# CE842170047_SHEET1.net
KiCad netlist of a schematic drawn in Altium Designer
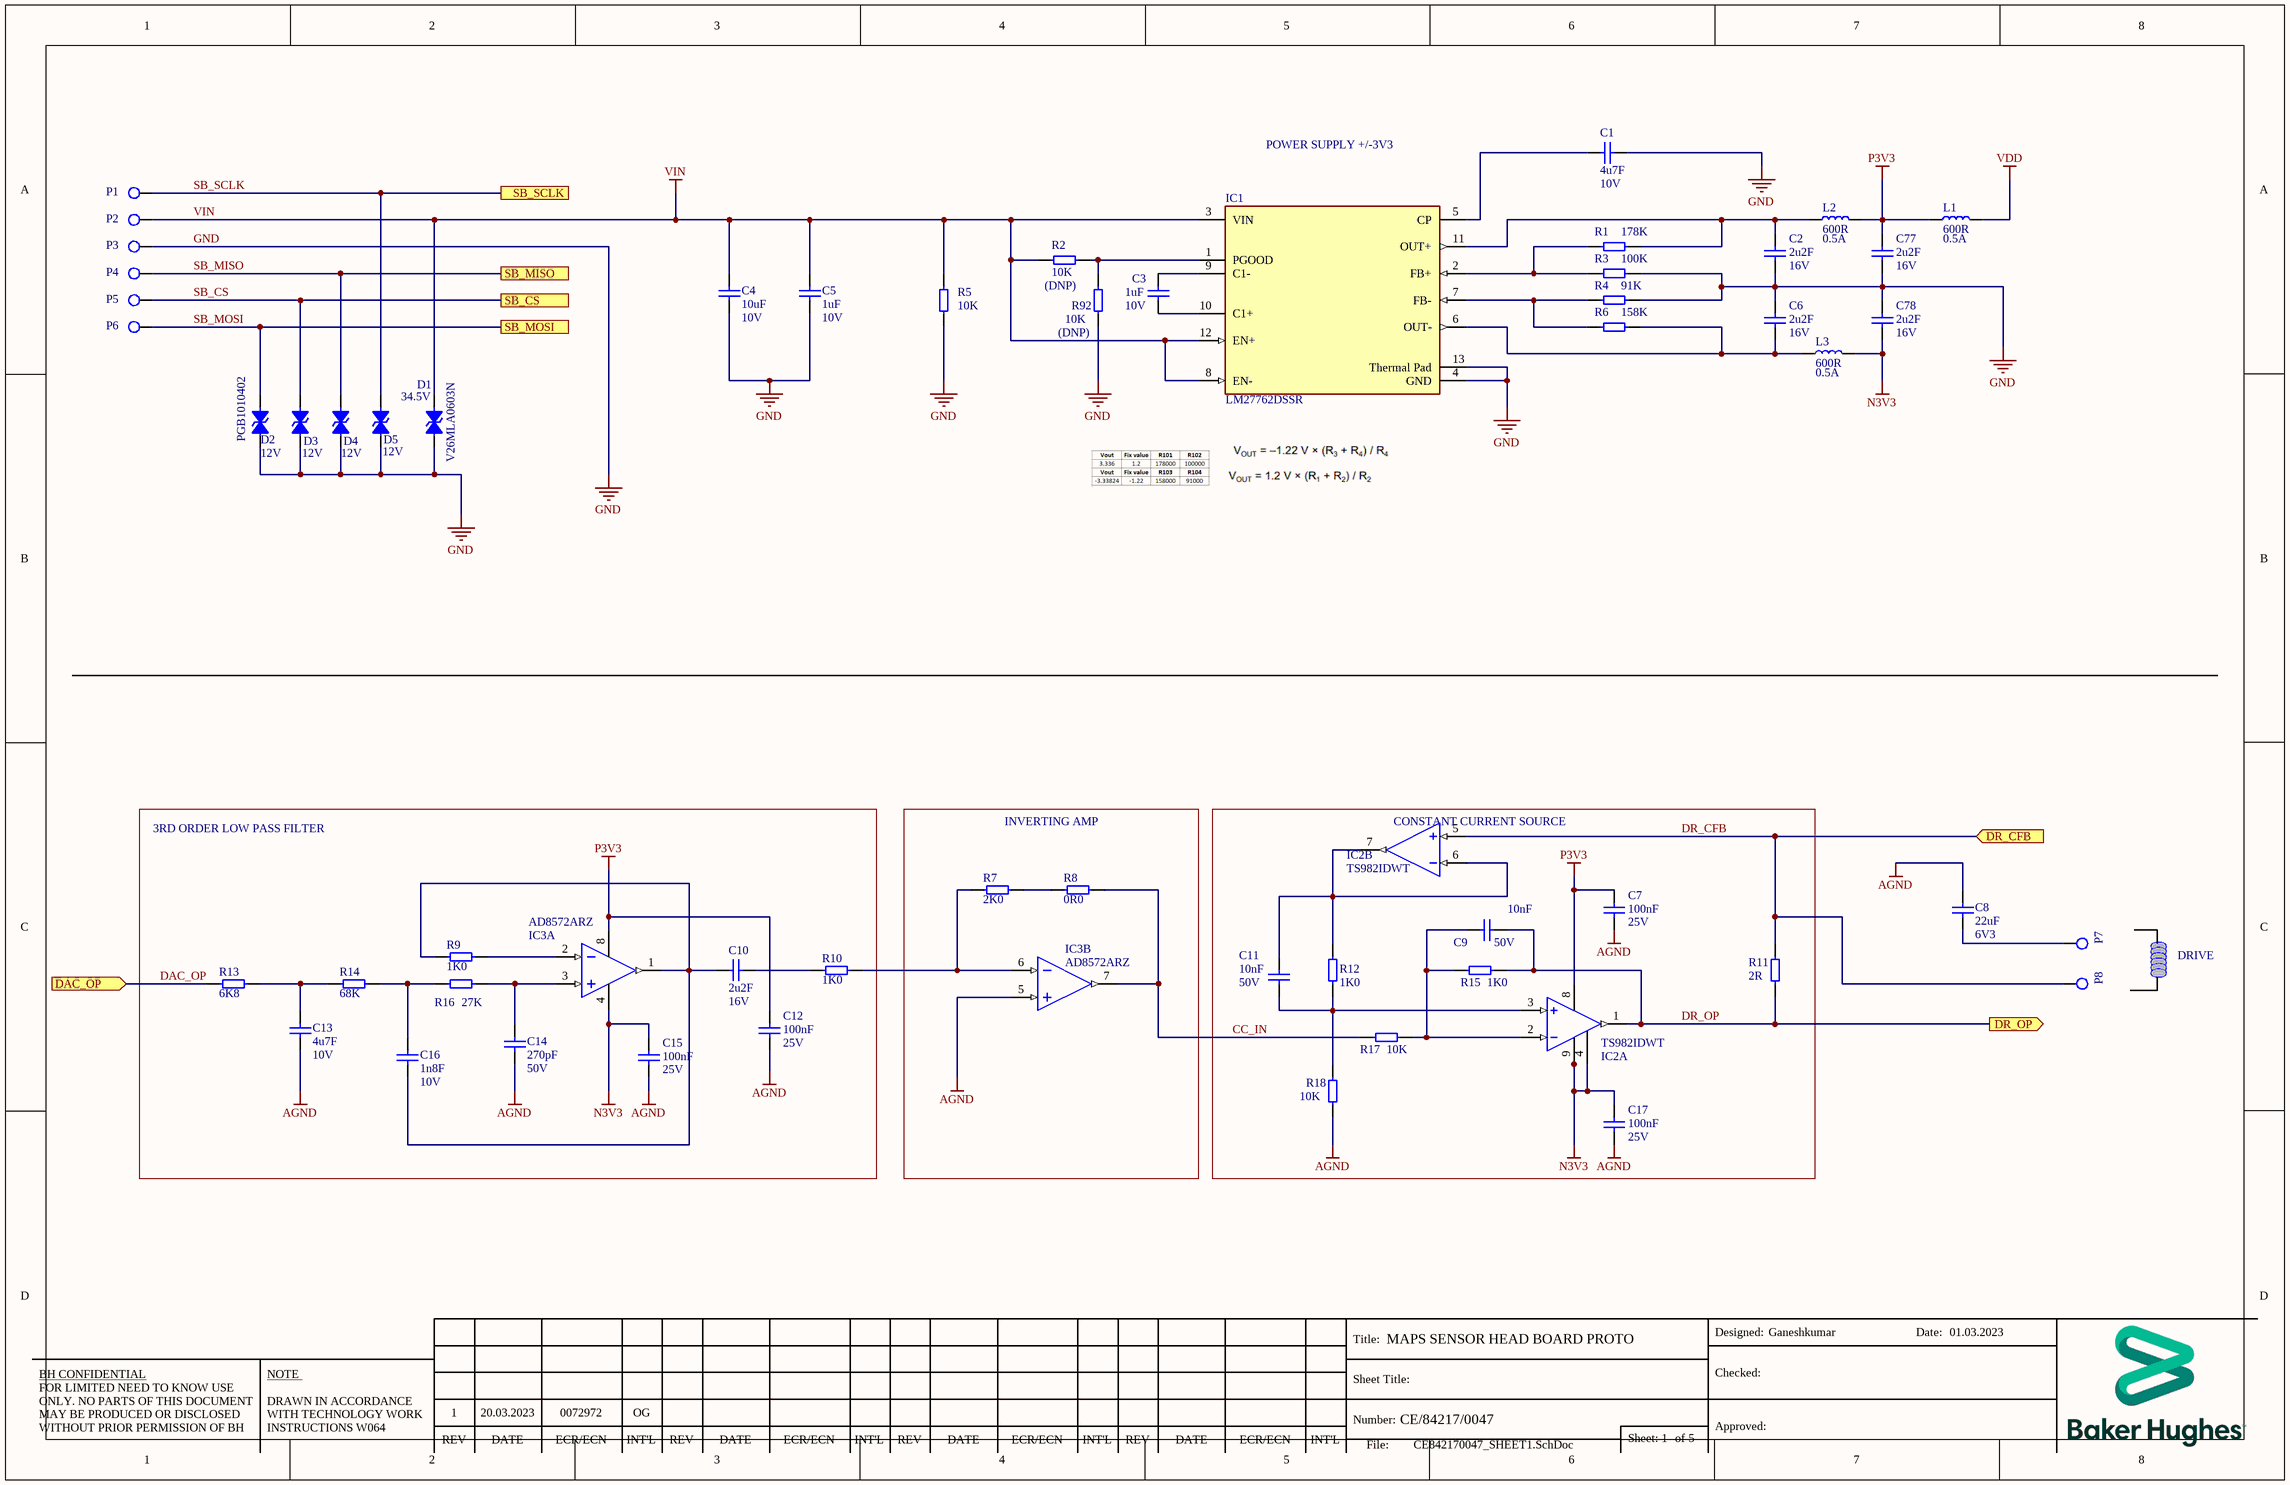
[diagram p0: CE842170047_SHEET1.SchDoc]

(export (version "E")
  (design (tool "Eeschema 10.0.6"))
  (components
    (comp (ref "C1")
      (value "4u7F")
      (footprint "C0603")
      (description "CAPACITOR_4u7F_10%_10V_0603")
      (fields
        (field (name "VOLTAGE") "10V")
        (field (name "PII_PARTNUMBER") "KK/96159/2666")
        (field (name "TOLERANCE") "10%")
      )
      (libsource (lib "AltiumComponents") (part "CAP_GENERIC"))
    )
    (comp (ref "C2")
      (value "2u2F")
      (footprint "C0603")
      (description "CAPACITOR CERAMIC 0603 16V 10% X5R 2u2")
      (fields
        (field (name "VOLTAGE") "16V")
        (field (name "PII_PARTNUMBER") "KK/96159/3634")
        (field (name "TOLERANCE") "10%")
      )
      (libsource (lib "AltiumComponents") (part "CAP_GENERIC"))
    )
    (comp (ref "C3")
      (value "1uF")
      (footprint "C0603")
      (description "CAPACITOR_1uF_+10%_10V_603")
      (fields
        (field (name "VOLTAGE") "10V")
        (field (name "PII_PARTNUMBER") "KK/96159/2601")
        (field (name "TOLERANCE") "10%")
      )
      (libsource (lib "AltiumComponents") (part "CAP_GENERIC"))
    )
    (comp (ref "C4")
      (value "10uF")
      (footprint "C0603")
      (description "CAPACITOR_10uF_10%_10V_0603")
      (fields
        (field (name "VOLTAGE") "10V")
        (field (name "PII_PARTNUMBER") "KK/96159/3701")
        (field (name "TOLERANCE") "10%")
      )
      (libsource (lib "AltiumComponents") (part "CAP_GENERIC"))
    )
    (comp (ref "C5")
      (value "1uF")
      (footprint "C0603")
      (description "CAPACITOR_1uF_+10%_10V_603")
      (fields
        (field (name "VOLTAGE") "10V")
        (field (name "PII_PARTNUMBER") "KK/96159/2601")
        (field (name "TOLERANCE") "10%")
      )
      (libsource (lib "AltiumComponents") (part "CAP_GENERIC"))
    )
    (comp (ref "C6")
      (value "2u2F")
      (footprint "C0603")
      (description "CAPACITOR CERAMIC 0603 16V 10% X5R 2u2")
      (fields
        (field (name "VOLTAGE") "16V")
        (field (name "PII_PARTNUMBER") "KK/96159/3634")
        (field (name "TOLERANCE") "10%")
      )
      (libsource (lib "AltiumComponents") (part "CAP_GENERIC"))
    )
    (comp (ref "C7")
      (value "100nF")
      (footprint "C0603")
      (description "CAPACITOR_100nF_+10%_25V_603")
      (fields
        (field (name "VOLTAGE") "25V")
        (field (name "PII_PARTNUMBER") "KK/96159/4501")
        (field (name "TOLERANCE") "10%")
      )
      (libsource (lib "AltiumComponents") (part "CAP_GENERIC"))
    )
    (comp (ref "C8")
      (value "22uF")
      (footprint "C0805")
      (description "CAPACITOR_22uF_20%_6V3_0805")
      (fields
        (field (name "VOLTAGE") "6V3")
        (field (name "PII_PARTNUMBER") "KK/96160/0734")
        (field (name "TOLERANCE") "20%")
      )
      (libsource (lib "AltiumComponents") (part "CAP_GENERIC"))
    )
    (comp (ref "C9")
      (value "10nF")
      (footprint "C0603")
      (description "CAPACITOR CERAMIC 0603 50V 10% X7R 10nF")
      (fields
        (field (name "VOLTAGE") "50V")
        (field (name "PII_PARTNUMBER") "KK/96159/0401")
        (field (name "TOLERANCE") "10%")
      )
      (libsource (lib "AltiumComponents") (part "CAP_GENERIC"))
    )
    (comp (ref "C10")
      (value "2u2F")
      (footprint "C0603")
      (description "CAPACITOR CERAMIC 0603 16V 10% X5R 2u2")
      (fields
        (field (name "VOLTAGE") "16V")
        (field (name "PII_PARTNUMBER") "KK/96159/3634")
        (field (name "TOLERANCE") "10%")
      )
      (libsource (lib "AltiumComponents") (part "CAP_GENERIC"))
    )
    (comp (ref "C11")
      (value "10nF")
      (footprint "C0603")
      (description "CAPACITOR CERAMIC 0603 50V 10% X7R 10nF")
      (fields
        (field (name "VOLTAGE") "50V")
        (field (name "PII_PARTNUMBER") "KK/96159/0401")
        (field (name "TOLERANCE") "10%")
      )
      (libsource (lib "AltiumComponents") (part "CAP_GENERIC"))
    )
    (comp (ref "C12")
      (value "100nF")
      (footprint "C0603")
      (description "CAPACITOR_100nF_+10%_25V_603")
      (fields
        (field (name "VOLTAGE") "25V")
        (field (name "PII_PARTNUMBER") "KK/96159/4501")
        (field (name "TOLERANCE") "10%")
      )
      (libsource (lib "AltiumComponents") (part "CAP_GENERIC"))
    )
    (comp (ref "C13")
      (value "4u7F")
      (footprint "C0603")
      (description "CAPACITOR_4u7F_10%_10V_0603")
      (fields
        (field (name "VOLTAGE") "10V")
        (field (name "PII_PARTNUMBER") "KK/96159/2666")
        (field (name "TOLERANCE") "10%")
      )
      (libsource (lib "AltiumComponents") (part "CAP_GENERIC"))
    )
    (comp (ref "C14")
      (value "270pF")
      (footprint "C0603")
      (description "CAPACITOR CER 0603 270pF 10% 50V X5R")
      (fields
        (field (name "VOLTAGE") "50V")
        (field (name "PII_PARTNUMBER") "KK/96159/0243")
        (field (name "TOLERANCE") "10%")
      )
      (libsource (lib "AltiumComponents") (part "CAP_GENERIC"))
    )
    (comp (ref "C15")
      (value "100nF")
      (footprint "C0603")
      (description "CAPACITOR_100nF_+10%_25V_603")
      (fields
        (field (name "VOLTAGE") "25V")
        (field (name "PII_PARTNUMBER") "KK/96159/4501")
        (field (name "TOLERANCE") "10%")
      )
      (libsource (lib "AltiumComponents") (part "CAP_GENERIC"))
    )
    (comp (ref "C16")
      (value "1n8F")
      (footprint "C0603")
      (description "CAPACITOR CER 0603 1n8F 10% 10V X5R")
      (fields
        (field (name "VOLTAGE") "10V")
        (field (name "PII_PARTNUMBER") "KK/96159/0325")
        (field (name "TOLERANCE") "10%")
      )
      (libsource (lib "AltiumComponents") (part "CAP_GENERIC"))
    )
    (comp (ref "C17")
      (value "100nF")
      (footprint "C0603")
      (description "CAPACITOR_100nF_+10%_25V_603")
      (fields
        (field (name "VOLTAGE") "25V")
        (field (name "PII_PARTNUMBER") "KK/96159/4501")
        (field (name "TOLERANCE") "10%")
      )
      (libsource (lib "AltiumComponents") (part "CAP_GENERIC"))
    )
    (comp (ref "C77")
      (value "2u2F")
      (footprint "C0603")
      (description "CAPACITOR CERAMIC 0603 16V 10% X5R 2u2")
      (fields
        (field (name "VOLTAGE") "16V")
        (field (name "PII_PARTNUMBER") "KK/96159/3634")
        (field (name "TOLERANCE") "10%")
      )
      (libsource (lib "AltiumComponents") (part "CAP_GENERIC"))
    )
    (comp (ref "C78")
      (value "2u2F")
      (footprint "C0603")
      (description "CAPACITOR CERAMIC 0603 16V 10% X5R 2u2")
      (fields
        (field (name "VOLTAGE") "16V")
        (field (name "PII_PARTNUMBER") "KK/96159/3634")
        (field (name "TOLERANCE") "10%")
      )
      (libsource (lib "AltiumComponents") (part "CAP_GENERIC"))
    )
    (comp (ref "D1")
      (value "34.5V")
      (footprint "R0603")
      (description "TVS,SMD,LITTLEFUSE,V26MLA0603N[20-26V]")
      (fields
        (field (name "MF_PARTNUMBER") "V26MLA0603N")
        (field (name "PII_PARTNUMBER") "KK/95070/0035")
        (field (name "VOLTAGE") "26V")
      )
      (libsource (lib "AltiumComponents") (part "TVS_DIODE_BIDIR"))
    )
    (comp (ref "D2")
      (value "KK/95070/0036")
      (footprint "ESD0402")
      (description "SUPPRESSOR ESD,SMD,0402,12VDC,LIF,PGB1010402")
      (fields
        (field (name "MF_PARTNUMBER") "PGB1010402")
        (field (name "VOLTAGE") "12V")
        (field (name "MANUFACTURER") "LITTELFUSE")
      )
      (libsource (lib "AltiumComponents") (part "TVS_DIODE_BIDIR"))
    )
    (comp (ref "D3")
      (value "KK/95070/0036")
      (footprint "ESD0402")
      (description "SUPPRESSOR ESD,SMD,0402,12VDC,LIF,PGB1010402")
      (fields
        (field (name "MF_PARTNUMBER") "PGB1010402")
        (field (name "VOLTAGE") "12V")
        (field (name "MANUFACTURER") "LITTELFUSE")
      )
      (libsource (lib "AltiumComponents") (part "TVS_DIODE_BIDIR"))
    )
    (comp (ref "D4")
      (value "KK/95070/0036")
      (footprint "ESD0402")
      (description "SUPPRESSOR ESD,SMD,0402,12VDC,LIF,PGB1010402")
      (fields
        (field (name "MF_PARTNUMBER") "PGB1010402")
        (field (name "VOLTAGE") "12V")
        (field (name "MANUFACTURER") "LITTELFUSE")
      )
      (libsource (lib "AltiumComponents") (part "TVS_DIODE_BIDIR"))
    )
    (comp (ref "D5")
      (value "KK/95070/0036")
      (footprint "ESD0402")
      (description "SUPPRESSOR ESD,SMD,0402,12VDC,LIF,PGB1010402")
      (fields
        (field (name "MF_PARTNUMBER") "PGB1010402")
        (field (name "VOLTAGE") "12V")
        (field (name "MANUFACTURER") "LITTELFUSE")
      )
      (libsource (lib "AltiumComponents") (part "TVS_DIODE_BIDIR"))
    )
    (comp (ref "IC1")
      (value "KK/95311/0117")
      (footprint "WSON-12")
      (description "SWITCHING REGULATOR")
      (fields
        (field (name "MANUFACTURER") "TEXAS INSTRUMENTS")
        (field (name "MANUFACTURER PART NUMBER") "LM27762DSSR")
        (field (name "MF_PARTNUMBER") "LM27762DSSR")
      )
      (libsource (lib "AltiumComponents") (part "LM27762"))
    )
    (comp (ref "IC2")
      (value "KK/95312/0246")
      (footprint "SOIC-8_EP")
      (description "DUAL BIPOLAR OPERATIONAL AMPLIFIER")
      (fields
        (field (name "MP") "TS982IDWT")
        (field (name "MF_PARTNUMBER") "TS982IDWT")
        (field (name "VOLTAGE") "5.5V")
      )
      (libsource (lib "AltiumComponents") (part "TS982"))
    )
    (comp (ref "IC3")
      (value "KK/95312/0244")
      (footprint "SOIC-8")
      (description "DUAL RAIL to RAIL OP AMP")
      (fields
        (field (name "MANUFACTURER") "Analog Devices")
        (field (name "GENERIC PART NUMBER") "AD8572")
        (field (name "MF_PARTNUMBER") "AD8572ARZ")
      )
      (libsource (lib "AltiumComponents") (part "AD8572"))
    )
    (comp (ref "L1")
      (value "600R")
      (footprint "L0603")
      (description "FERRIT BEADS 0603 600R 0.5A 25%")
      (fields
        (field (name "PII_PARTNUMBER") "KK/97900/1033")
        (field (name "MF_PARTNUMBER") "742863160")
        (field (name "POWER") "0.5A")
      )
      (libsource (lib "AltiumComponents") (part "INDUCTOR_GENERIC"))
    )
    (comp (ref "L2")
      (value "600R")
      (footprint "L0603")
      (description "FERRIT BEADS 0603 600R 0.5A 25%")
      (fields
        (field (name "PII_PARTNUMBER") "KK/97900/1033")
        (field (name "MF_PARTNUMBER") "742863160")
        (field (name "POWER") "0.5A")
      )
      (libsource (lib "AltiumComponents") (part "INDUCTOR_GENERIC"))
    )
    (comp (ref "L3")
      (value "600R")
      (footprint "L0603")
      (description "FERRIT BEADS 0603 600R 0.5A 25%")
      (fields
        (field (name "PII_PARTNUMBER") "KK/97900/1033")
        (field (name "MF_PARTNUMBER") "742863160")
        (field (name "POWER") "0.5A")
      )
      (libsource (lib "AltiumComponents") (part "INDUCTOR_GENERIC"))
    )
    (comp (ref "P1")
      (value "TESTPAD1")
      (footprint "P0.8xH0.5")
      (description "P0.8 X H0.5 X 0.9SM")
      (fields (field (name "MANUFACTURER") "PCB MANUFACTURER"))
      (libsource (lib "AltiumComponents") (part "TP_GENERIC"))
    )
    (comp (ref "P2")
      (value "TESTPAD1")
      (footprint "P0.8xH0.5")
      (description "P0.8 X H0.5 X 0.9SM")
      (fields (field (name "MANUFACTURER") "PCB MANUFACTURER"))
      (libsource (lib "AltiumComponents") (part "TP_GENERIC"))
    )
    (comp (ref "P3")
      (value "TESTPAD1")
      (footprint "P0.8xH0.5")
      (description "P0.8 X H0.5 X 0.9SM")
      (fields (field (name "MANUFACTURER") "PCB MANUFACTURER"))
      (libsource (lib "AltiumComponents") (part "TP_GENERIC"))
    )
    (comp (ref "P4")
      (value "TESTPAD1")
      (footprint "P0.8xH0.5")
      (description "P0.8 X H0.5 X 0.9SM")
      (fields (field (name "MANUFACTURER") "PCB MANUFACTURER"))
      (libsource (lib "AltiumComponents") (part "TP_GENERIC"))
    )
    (comp (ref "P5")
      (value "TESTPAD1")
      (footprint "P0.8xH0.5")
      (description "P0.8 X H0.5 X 0.9SM")
      (fields (field (name "MANUFACTURER") "PCB MANUFACTURER"))
      (libsource (lib "AltiumComponents") (part "TP_GENERIC"))
    )
    (comp (ref "P6")
      (value "TESTPAD1")
      (footprint "P0.8xH0.5")
      (description "P0.8 X H0.5 X 0.9SM")
      (fields (field (name "MANUFACTURER") "PCB MANUFACTURER"))
      (libsource (lib "AltiumComponents") (part "TP_GENERIC"))
    )
    (comp (ref "P7")
      (value "TESTPAD1")
      (footprint "P0.8xH0.5")
      (description "P0.8 X H0.5 X 0.9SM")
      (fields (field (name "MANUFACTURER") "PCB MANUFACTURER"))
      (libsource (lib "AltiumComponents") (part "TP_GENERIC"))
    )
    (comp (ref "P8")
      (value "TESTPAD1")
      (footprint "P0.8xH0.5")
      (description "P0.8 X H0.5 X 0.9SM")
      (fields (field (name "MANUFACTURER") "PCB MANUFACTURER"))
      (libsource (lib "AltiumComponents") (part "TP_GENERIC"))
    )
    (comp (ref "R1")
      (value "178K")
      (footprint "R0603")
      (description "RESISTOR 0603 0.063W 0.1% 178K")
      (fields (field (name "PII_PARTNUMBER") "KK/96059/0725") (field (name "TOLERANCE") "0.1%"))
      (libsource (lib "AltiumComponents") (part "RES_GENERIC"))
    )
    (comp (ref "R2")
      (value "10K")
      (footprint "R0603")
      (description "RESISTOR_10K_1%_0603J_63mW")
      (fields (field (name "PII_PARTNUMBER") "KK/96059/0601") (field (name "TOLERANCE") "1%"))
      (libsource (lib "AltiumComponents") (part "RES_GENERIC"))
    )
    (comp (ref "R3")
      (value "100K")
      (footprint "R0603")
      (description "RESISTOR_100K_1%_0603J_63mW")
      (fields (field (name "PII_PARTNUMBER") "KK/96059/0701") (field (name "TOLERANCE") "1%"))
      (libsource (lib "AltiumComponents") (part "RES_GENERIC"))
    )
    (comp (ref "R4")
      (value "91K")
      (footprint "R0603")
      (description "RESISTOR 0603 0.063W 1% 91K")
      (fields (field (name "PII_PARTNUMBER") "KK/96059/1693") (field (name "TOLERANCE") "1%"))
      (libsource (lib "AltiumComponents") (part "RES_GENERIC"))
    )
    (comp (ref "R5")
      (value "10K")
      (footprint "R0603")
      (description "RESISTOR_10K_1%_0603J_63mW")
      (fields (field (name "PII_PARTNUMBER") "KK/96059/0601") (field (name "TOLERANCE") "1%"))
      (libsource (lib "") (part "RES_GENERIC_3"))
    )
    (comp (ref "R6")
      (value "158K")
      (footprint "R0603")
      (description "RESISTOR_158K_1%_0603J_63mW")
      (fields (field (name "PII_PARTNUMBER") "KK/96059/0720") (field (name "TOLERANCE") "1%"))
      (libsource (lib "AltiumComponents") (part "RES_GENERIC"))
    )
    (comp (ref "R7")
      (value "2K0")
      (footprint "R0603")
      (description "RESISTOR_2K_1%_0603J_63m2")
      (fields (field (name "PII_PARTNUMBER") "KK/96059/0530") (field (name "TOLERANCE") "1%"))
      (libsource (lib "AltiumComponents") (part "RES_GENERIC"))
    )
    (comp (ref "R8")
      (value "0R0")
      (footprint "R0603")
      (description "ZERO OHM LINK")
      (fields (field (name "PII_PARTNUMBER") "KK/96059/0000") (field (name "POWER") "63mW"))
      (libsource (lib "AltiumComponents") (part "RES_GENERIC"))
    )
    (comp (ref "R9")
      (value "1K0")
      (footprint "R0603")
      (description "RESISTOR_1K0_1%_0603J_63mW")
      (fields (field (name "PII_PARTNUMBER") "KK/96059/0501") (field (name "TOLERANCE") "1%"))
      (libsource (lib "AltiumComponents") (part "RES_GENERIC"))
    )
    (comp (ref "R10")
      (value "1K0")
      (footprint "R0603")
      (description "RESISTOR_1K0_1%_0603J_63mW")
      (fields (field (name "PII_PARTNUMBER") "KK/96059/0501") (field (name "TOLERANCE") "1%"))
      (libsource (lib "AltiumComponents") (part "RES_GENERIC"))
    )
    (comp (ref "R11")
      (value "2R")
      (footprint "R2512")
      (description "RESISTOR 2R 2512 1% 1W")
      (fields (field (name "PII_PARTNUMBER") "KK/96090/0230") (field (name "TOLERANCE") "1%"))
      (libsource (lib "") (part "RES_GENERIC_2"))
    )
    (comp (ref "R12")
      (value "1K0")
      (footprint "R0603")
      (description "RESISTOR_1K0_1%_0603J_63mW")
      (fields (field (name "PII_PARTNUMBER") "KK/96059/0501") (field (name "TOLERANCE") "1%"))
      (libsource (lib "") (part "RES_GENERIC_2"))
    )
    (comp (ref "R13")
      (value "6K8")
      (footprint "R0603")
      (description "RESISTOR 0603 0.063W 1% 6K8")
      (fields (field (name "PII_PARTNUMBER") "KK/96059/0581") (field (name "TOLERANCE") "1%"))
      (libsource (lib "AltiumComponents") (part "RES_GENERIC"))
    )
    (comp (ref "R14")
      (value "68K")
      (footprint "R0603")
      (description "RESISTOR_68K_1%_0603J_63mW")
      (fields (field (name "PII_PARTNUMBER") "KK/96059/0681") (field (name "TOLERANCE") "1%"))
      (libsource (lib "AltiumComponents") (part "RES_GENERIC"))
    )
    (comp (ref "R15")
      (value "1K0")
      (footprint "R0603")
      (description "RESISTOR_1K0_1%_0603J_63mW")
      (fields (field (name "PII_PARTNUMBER") "KK/96059/0501") (field (name "TOLERANCE") "1%"))
      (libsource (lib "") (part "RES_GENERIC_1"))
    )
    (comp (ref "R16")
      (value "27K")
      (footprint "R0603")
      (description "RESISTOR 0603 0.063W 1% 27K")
      (fields (field (name "PII_PARTNUMBER") "KK/96059/0643") (field (name "TOLERANCE") "1%"))
      (libsource (lib "AltiumComponents") (part "RES_GENERIC"))
    )
    (comp (ref "R17")
      (value "10K")
      (footprint "R0603")
      (description "RESISTOR_10K_1%_0603J_63mW")
      (fields (field (name "PII_PARTNUMBER") "KK/96059/0601") (field (name "TOLERANCE") "1%"))
      (libsource (lib "") (part "RES_GENERIC_1"))
    )
    (comp (ref "R18")
      (value "10K")
      (footprint "R0603")
      (description "RESISTOR_10K_1%_0603J_63mW")
      (fields (field (name "PII_PARTNUMBER") "KK/96059/0601") (field (name "TOLERANCE") "1%"))
      (libsource (lib "") (part "RES_GENERIC_2"))
    )
    (comp (ref "R92")
      (value "10K")
      (footprint "R0603")
      (description "RESISTOR_10K_1%_0603J_63mW")
      (fields (field (name "PII_PARTNUMBER") "KK/96059/0601") (field (name "TOLERANCE") "1%"))
      (libsource (lib "") (part "RES_GENERIC_2"))
    )
  )
  (nets
    (net (code "1") (name "/CC_IN") (class "Default")
      (node (ref "IC3") (pin "7") (pinfunction "OUT_B_7") (pintype "output"))
      (node (ref "R17") (pin "2") (pinfunction "2_2") (pintype "passive"))
      (node (ref "R8") (pin "2") (pinfunction "2_2") (pintype "passive"))
    )
    (net (code "2") (name "/DAC_OP") (class "Default")
      (node (ref "R13") (pin "1") (pinfunction "1_1") (pintype "passive"))
    )
    (net (code "3") (name "/DR_CFB") (class "Default")
      (node (ref "IC2") (pin "5") (pinfunction "NON_INVERTING_INPUT_2_5") (pintype "input"))
      (node (ref "P8") (pin "1") (pinfunction "1_1") (pintype "passive"))
      (node (ref "R11") (pin "2") (pinfunction "2_2") (pintype "passive"))
    )
    (net (code "4") (name "/DR_OP") (class "Default")
      (node (ref "C9") (pin "2") (pinfunction "2_2") (pintype "passive"))
      (node (ref "IC2") (pin "1") (pinfunction "OUTPUT1_1") (pintype "output"))
      (node (ref "R11") (pin "1") (pinfunction "1_1") (pintype "passive"))
      (node (ref "R15") (pin "1") (pinfunction "1_1") (pintype "passive"))
    )
    (net (code "5") (name "/SB_CS") (class "Default")
      (node (ref "D3") (pin "2") (pinfunction "2_2") (pintype "passive"))
      (node (ref "P5") (pin "1") (pinfunction "1_1") (pintype "passive"))
    )
    (net (code "6") (name "/SB_MISO") (class "Default")
      (node (ref "D4") (pin "2") (pinfunction "2_2") (pintype "passive"))
      (node (ref "P4") (pin "1") (pinfunction "1_1") (pintype "passive"))
    )
    (net (code "7") (name "/SB_MOSI") (class "Default")
      (node (ref "D2") (pin "2") (pinfunction "2_2") (pintype "passive"))
      (node (ref "P6") (pin "1") (pinfunction "1_1") (pintype "passive"))
    )
    (net (code "8") (name "/SB_SCLK") (class "Default")
      (node (ref "D5") (pin "2") (pinfunction "2_2") (pintype "passive"))
      (node (ref "P1") (pin "1") (pinfunction "1_1") (pintype "passive"))
    )
    (net (code "9") (name "AGND") (class "Default")
      (node (ref "C12") (pin "2") (pinfunction "2_2") (pintype "passive"))
      (node (ref "C13") (pin "2") (pinfunction "2_2") (pintype "passive"))
      (node (ref "C14") (pin "2") (pinfunction "2_2") (pintype "passive"))
      (node (ref "C15") (pin "2") (pinfunction "2_2") (pintype "passive"))
      (node (ref "C17") (pin "2") (pinfunction "2_2") (pintype "passive"))
      (node (ref "C7") (pin "2") (pinfunction "2_2") (pintype "passive"))
      (node (ref "C8") (pin "1") (pinfunction "1_1") (pintype "passive"))
      (node (ref "IC3") (pin "5") (pinfunction "+IN_B_5") (pintype "input"))
      (node (ref "R18") (pin "1") (pinfunction "1_1") (pintype "passive"))
    )
    (net (code "10") (name "GND") (class "Default")
      (node (ref "C1") (pin "2") (pinfunction "2_2") (pintype "passive"))
      (node (ref "C2") (pin "2") (pinfunction "2_2") (pintype "passive"))
      (node (ref "C4") (pin "2") (pinfunction "2_2") (pintype "passive"))
      (node (ref "C5") (pin "2") (pinfunction "2_2") (pintype "passive"))
      (node (ref "C6") (pin "1") (pinfunction "1_1") (pintype "passive"))
      (node (ref "C77") (pin "2") (pinfunction "2_2") (pintype "passive"))
      (node (ref "C78") (pin "1") (pinfunction "1_1") (pintype "passive"))
      (node (ref "D1") (pin "1") (pinfunction "1_1") (pintype "passive"))
      (node (ref "D2") (pin "1") (pinfunction "1_1") (pintype "passive"))
      (node (ref "D3") (pin "1") (pinfunction "1_1") (pintype "passive"))
      (node (ref "D4") (pin "1") (pinfunction "1_1") (pintype "passive"))
      (node (ref "D5") (pin "1") (pinfunction "1_1") (pintype "passive"))
      (node (ref "IC1") (pin "13") (pinfunction "Thermal_Pad_13") (pintype "passive"))
      (node (ref "IC1") (pin "4") (pinfunction "GND_4") (pintype "power_in"))
      (node (ref "P3") (pin "1") (pinfunction "1_1") (pintype "passive"))
      (node (ref "R3") (pin "2") (pinfunction "2_2") (pintype "passive"))
      (node (ref "R4") (pin "2") (pinfunction "2_2") (pintype "passive"))
      (node (ref "R5") (pin "2") (pinfunction "2_2") (pintype "passive"))
      (node (ref "R92") (pin "1") (pinfunction "1_1") (pintype "passive"))
    )
    (net (code "11") (name "N3V3") (class "Default")
      (node (ref "C15") (pin "1") (pinfunction "1_1") (pintype "passive"))
      (node (ref "C17") (pin "1") (pinfunction "1_1") (pintype "passive"))
      (node (ref "C78") (pin "2") (pinfunction "2_2") (pintype "passive"))
      (node (ref "IC2") (pin "4") (pinfunction "VCC-_4") (pintype "power_in"))
      (node (ref "IC2") (pin "9") (pinfunction "VCC-_9") (pintype "power_in"))
      (node (ref "IC3") (pin "4") (pinfunction "-V_4") (pintype "power_in"))
      (node (ref "L3") (pin "2") (pinfunction "2_2") (pintype "passive"))
    )
    (net (code "12") (name "Net-(C8-Pad2)") (class "Default")
      (node (ref "C8") (pin "2") (pinfunction "2_2") (pintype "passive"))
      (node (ref "P7") (pin "1") (pinfunction "1_1") (pintype "passive"))
    )
    (net (code "13") (name "Net-(C10-Pad2)") (class "Default")
      (node (ref "C10") (pin "2") (pinfunction "2_2") (pintype "passive"))
      (node (ref "R10") (pin "1") (pinfunction "1_1") (pintype "passive"))
    )
    (net (code "14") (name "Net-(C13-Pad1)") (class "Default")
      (node (ref "C13") (pin "1") (pinfunction "1_1") (pintype "passive"))
      (node (ref "R13") (pin "2") (pinfunction "2_2") (pintype "passive"))
      (node (ref "R14") (pin "1") (pinfunction "1_1") (pintype "passive"))
    )
    (net (code "15") (name "Net-(C16-Pad1)") (class "Default")
      (node (ref "C16") (pin "1") (pinfunction "1_1") (pintype "passive"))
      (node (ref "R14") (pin "2") (pinfunction "2_2") (pintype "passive"))
      (node (ref "R16") (pin "1") (pinfunction "1_1") (pintype "passive"))
    )
    (net (code "16") (name "Net-(IC1-C1+)") (class "Default")
      (node (ref "C3") (pin "2") (pinfunction "2_2") (pintype "passive"))
      (node (ref "IC1") (pin "10") (pinfunction "C1+_10") (pintype "passive"))
    )
    (net (code "17") (name "Net-(IC1-C1-)") (class "Default")
      (node (ref "C3") (pin "1") (pinfunction "1_1") (pintype "passive"))
      (node (ref "IC1") (pin "9") (pinfunction "C1-_9") (pintype "passive"))
    )
    (net (code "18") (name "Net-(IC1-CP)") (class "Default")
      (node (ref "C1") (pin "1") (pinfunction "1_1") (pintype "passive"))
      (node (ref "IC1") (pin "5") (pinfunction "CP_5") (pintype "power_in"))
    )
    (net (code "19") (name "Net-(IC1-FB+)") (class "Default")
      (node (ref "IC1") (pin "2") (pinfunction "FB+_2") (pintype "input"))
      (node (ref "R1") (pin "1") (pinfunction "1_1") (pintype "passive"))
      (node (ref "R3") (pin "1") (pinfunction "1_1") (pintype "passive"))
    )
    (net (code "20") (name "Net-(IC1-FB-)") (class "Default")
      (node (ref "IC1") (pin "7") (pinfunction "FB-_7") (pintype "input"))
      (node (ref "R4") (pin "1") (pinfunction "1_1") (pintype "passive"))
      (node (ref "R6") (pin "1") (pinfunction "1_1") (pintype "passive"))
    )
    (net (code "21") (name "Net-(IC1-OUT+)") (class "Default")
      (node (ref "C2") (pin "1") (pinfunction "1_1") (pintype "passive"))
      (node (ref "IC1") (pin "11") (pinfunction "OUT+_11") (pintype "output"))
      (node (ref "L2") (pin "1") (pinfunction "1_1") (pintype "passive"))
      (node (ref "R1") (pin "2") (pinfunction "2_2") (pintype "passive"))
    )
    (net (code "22") (name "Net-(IC1-OUT-)") (class "Default")
      (node (ref "C6") (pin "2") (pinfunction "2_2") (pintype "passive"))
      (node (ref "IC1") (pin "6") (pinfunction "OUT-_6") (pintype "output"))
      (node (ref "L3") (pin "1") (pinfunction "1_1") (pintype "passive"))
      (node (ref "R6") (pin "2") (pinfunction "2_2") (pintype "passive"))
    )
    (net (code "23") (name "Net-(IC1-PGOOD)") (class "Default")
      (node (ref "IC1") (pin "1") (pinfunction "PGOOD_1") (pintype "open_collector"))
      (node (ref "R2") (pin "2") (pinfunction "2_2") (pintype "passive"))
      (node (ref "R92") (pin "2") (pinfunction "2_2") (pintype "passive"))
    )
    (net (code "24") (name "Net-(IC2A-INVERTING_INPUT_1)") (class "Default")
      (node (ref "C9") (pin "1") (pinfunction "1_1") (pintype "passive"))
      (node (ref "IC2") (pin "2") (pinfunction "INVERTING_INPUT_1_2") (pintype "input"))
      (node (ref "R15") (pin "2") (pinfunction "2_2") (pintype "passive"))
      (node (ref "R17") (pin "1") (pinfunction "1_1") (pintype "passive"))
    )
    (net (code "25") (name "Net-(IC2A-NON_INVERTING_INPUT_1)") (class "Default")
      (node (ref "C11") (pin "2") (pinfunction "2_2") (pintype "passive"))
      (node (ref "IC2") (pin "3") (pinfunction "NON_INVERTING_INPUT_1_3") (pintype "input"))
      (node (ref "R12") (pin "1") (pinfunction "1_1") (pintype "passive"))
      (node (ref "R18") (pin "2") (pinfunction "2_2") (pintype "passive"))
    )
    (net (code "26") (name "Net-(IC2B-INVERTING_INPUT_2)") (class "Default")
      (node (ref "C11") (pin "1") (pinfunction "1_1") (pintype "passive"))
      (node (ref "IC2") (pin "6") (pinfunction "INVERTING_INPUT_2_6") (pintype "input"))
      (node (ref "IC2") (pin "7") (pinfunction "OUTPUT2_7") (pintype "output"))
      (node (ref "R12") (pin "2") (pinfunction "2_2") (pintype "passive"))
    )
    (net (code "27") (name "Net-(IC3A-+IN_A)") (class "Default")
      (node (ref "C14") (pin "1") (pinfunction "1_1") (pintype "passive"))
      (node (ref "IC3") (pin "3") (pinfunction "+IN_A_3") (pintype "input"))
      (node (ref "R16") (pin "2") (pinfunction "2_2") (pintype "passive"))
    )
    (net (code "28") (name "Net-(IC3A--IN_A)") (class "Default")
      (node (ref "IC3") (pin "2") (pinfunction "-IN_A_2") (pintype "input"))
      (node (ref "R9") (pin "2") (pinfunction "2_2") (pintype "passive"))
    )
    (net (code "29") (name "Net-(IC3A-OUT_A)") (class "Default")
      (node (ref "C10") (pin "1") (pinfunction "1_1") (pintype "passive"))
      (node (ref "C16") (pin "2") (pinfunction "2_2") (pintype "passive"))
      (node (ref "IC3") (pin "1") (pinfunction "OUT_A_1") (pintype "output"))
      (node (ref "R9") (pin "1") (pinfunction "1_1") (pintype "passive"))
    )
    (net (code "30") (name "Net-(IC3B--IN_B)") (class "Default")
      (node (ref "IC3") (pin "6") (pinfunction "-IN_B_6") (pintype "input"))
      (node (ref "R10") (pin "2") (pinfunction "2_2") (pintype "passive"))
      (node (ref "R7") (pin "1") (pinfunction "1_1") (pintype "passive"))
    )
    (net (code "31") (name "Net-(R7-Pad2)") (class "Default")
      (node (ref "R7") (pin "2") (pinfunction "2_2") (pintype "passive"))
      (node (ref "R8") (pin "1") (pinfunction "1_1") (pintype "passive"))
    )
    (net (code "32") (name "P3V3") (class "Default")
      (node (ref "C12") (pin "1") (pinfunction "1_1") (pintype "passive"))
      (node (ref "C7") (pin "1") (pinfunction "1_1") (pintype "passive"))
      (node (ref "C77") (pin "1") (pinfunction "1_1") (pintype "passive"))
      (node (ref "IC2") (pin "8") (pinfunction "VCC+_8") (pintype "power_in"))
      (node (ref "IC3") (pin "8") (pinfunction "+V_8") (pintype "power_in"))
      (node (ref "L1") (pin "1") (pinfunction "1_1") (pintype "passive"))
      (node (ref "L2") (pin "2") (pinfunction "2_2") (pintype "passive"))
    )
    (net (code "33") (name "VDD") (class "Default")
      (node (ref "L1") (pin "2") (pinfunction "2_2") (pintype "passive"))
    )
    (net (code "34") (name "VIN") (class "Default")
      (node (ref "C4") (pin "1") (pinfunction "1_1") (pintype "passive"))
      (node (ref "C5") (pin "1") (pinfunction "1_1") (pintype "passive"))
      (node (ref "D1") (pin "2") (pinfunction "2_2") (pintype "passive"))
      (node (ref "IC1") (pin "12") (pinfunction "EN+_12") (pintype "input"))
      (node (ref "IC1") (pin "3") (pinfunction "VIN_3") (pintype "power_in"))
      (node (ref "IC1") (pin "8") (pinfunction "EN-_8") (pintype "input"))
      (node (ref "P2") (pin "1") (pinfunction "1_1") (pintype "passive"))
      (node (ref "R2") (pin "1") (pinfunction "1_1") (pintype "passive"))
      (node (ref "R5") (pin "1") (pinfunction "1_1") (pintype "passive"))
    )
  )
)
